# Board.net
KiCad netlist of a schematic drawn in EAGLE
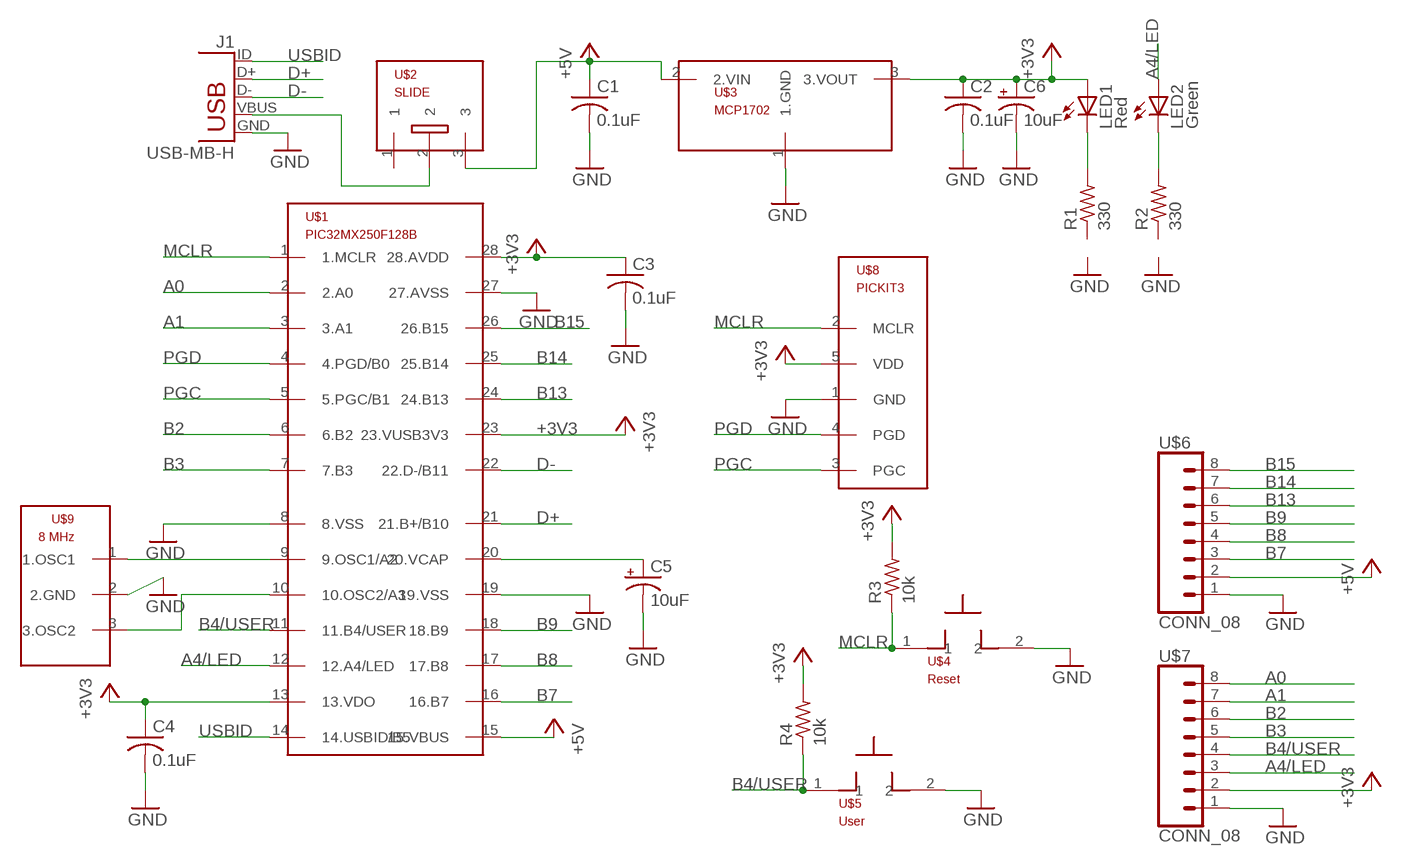
[diagram p0: schematic, sheet 1]

(export (version "E")
  (design (tool "Eeschema 10.0.6"))
  (components
    (comp (ref "C1")
      (value "0.1uF")
      (footprint "eagle-import:C025-025X050")
      (libsource (lib "eagle-import") (part "C-US025-025X050"))
    )
    (comp (ref "C2")
      (value "0.1uF")
      (footprint "eagle-import:C025-025X050")
      (libsource (lib "eagle-import") (part "C-US025-025X050"))
    )
    (comp (ref "C3")
      (value "0.1uF")
      (footprint "eagle-import:C025-025X050")
      (libsource (lib "eagle-import") (part "C-US025-025X050"))
    )
    (comp (ref "C4")
      (value "0.1uF")
      (footprint "eagle-import:C025-025X050")
      (libsource (lib "eagle-import") (part "C-US025-025X050"))
    )
    (comp (ref "C5")
      (value "10uF")
      (footprint "eagle-import:B45181B")
      (libsource (lib "eagle-import") (part "CPOL-USB45181B"))
    )
    (comp (ref "C6")
      (value "10uF")
      (footprint "eagle-import:B45181B")
      (libsource (lib "eagle-import") (part "CPOL-USB45181B"))
    )
    (comp (ref "J1")
      (value "USB-MB-H")
      (footprint "eagle-import:USB-MB-H")
      (libsource (lib "eagle-import") (part "USB-MB-H"))
    )
    (comp (ref "LED1")
      (value "Red")
      (footprint "eagle-import:LED3MM")
      (libsource (lib "eagle-import") (part "LED3MM"))
    )
    (comp (ref "LED2")
      (value "Green")
      (footprint "eagle-import:LED3MM")
      (libsource (lib "eagle-import") (part "LED3MM"))
    )
    (comp (ref "R1")
      (value "330")
      (footprint "eagle-import:0207_10")
      (libsource (lib "eagle-import") (part "R-US_0207/10"))
    )
    (comp (ref "R2")
      (value "330")
      (footprint "eagle-import:0207_10")
      (libsource (lib "eagle-import") (part "R-US_0207/10"))
    )
    (comp (ref "R3")
      (value "10k")
      (footprint "eagle-import:0207_10")
      (libsource (lib "eagle-import") (part "R-US_0207/10"))
    )
    (comp (ref "R4")
      (value "10k")
      (footprint "eagle-import:0207_10")
      (libsource (lib "eagle-import") (part "R-US_0207/10"))
    )
    (comp (ref "U$1")
      (value "PIC32MX250F128B")
      (footprint "eagle-import:DIL28-3")
      (libsource (lib "eagle-import") (part "PIC32MX250F128B"))
    )
    (comp (ref "U$2")
      (value "SLIDE")
      (footprint "eagle-import:SLIDE")
      (libsource (lib "eagle-import") (part "SLIDE"))
    )
    (comp (ref "U$3")
      (value "MCP1702")
      (footprint "eagle-import:TO92")
      (libsource (lib "eagle-import") (part "MCP1702"))
    )
    (comp (ref "U$4")
      (value "Reset")
      (footprint "eagle-import:PB")
      (libsource (lib "eagle-import") (part "PB"))
    )
    (comp (ref "U$5")
      (value "User")
      (footprint "eagle-import:PB")
      (libsource (lib "eagle-import") (part "PB"))
    )
    (comp (ref "U$6")
      (value "CONN_08")
      (footprint "eagle-import:1X08")
      (libsource (lib "eagle-import") (part "CONN_08"))
    )
    (comp (ref "U$7")
      (value "CONN_08")
      (footprint "eagle-import:1X08")
      (libsource (lib "eagle-import") (part "CONN_08"))
    )
    (comp (ref "U$8")
      (value "PICKIT3")
      (footprint "eagle-import:1X05")
      (libsource (lib "eagle-import") (part "PICKIT3"))
    )
    (comp (ref "U$9")
      (value "8 MHz")
      (footprint "eagle-import:OSC")
      (libsource (lib "eagle-import") (part "OSC"))
    )
  )
  (nets
    (net (code "1") (name "+3V3") (class "Default")
      (node (ref "C2") (pin "1") (pinfunction "1_1") (pintype "passive"))
      (node (ref "C3") (pin "1") (pinfunction "1_1") (pintype "passive"))
      (node (ref "C4") (pin "1") (pinfunction "1_1") (pintype "passive"))
      (node (ref "C6") (pin "+") (pinfunction "+_+") (pintype "passive"))
      (node (ref "LED1") (pin "A") (pinfunction "A_A") (pintype "passive"))
      (node (ref "R3") (pin "2") (pinfunction "2_2") (pintype "passive"))
      (node (ref "R4") (pin "2") (pinfunction "2_2") (pintype "passive"))
      (node (ref "U$1") (pin "13") (pinfunction "13.VDO_13") (pintype "bidirectional"))
      (node (ref "U$1") (pin "23") (pinfunction "23.VUSB3V3_23") (pintype "bidirectional"))
      (node (ref "U$1") (pin "28") (pinfunction "28.AVDD_28") (pintype "bidirectional"))
      (node (ref "U$3") (pin "3") (pinfunction "3.VOUT_3") (pintype "bidirectional"))
      (node (ref "U$7") (pin "2") (pinfunction "2_2") (pintype "passive"))
      (node (ref "U$8") (pin "5") (pinfunction "VDD_5") (pintype "bidirectional"))
    )
    (net (code "2") (name "+5V") (class "Default")
      (node (ref "C1") (pin "1") (pinfunction "1_1") (pintype "passive"))
      (node (ref "U$1") (pin "15") (pinfunction "15.VBUS_15") (pintype "bidirectional"))
      (node (ref "U$2") (pin "3") (pinfunction "3_3") (pintype "bidirectional"))
      (node (ref "U$3") (pin "2") (pinfunction "2.VIN_2") (pintype "bidirectional"))
      (node (ref "U$6") (pin "2") (pinfunction "2_2") (pintype "passive"))
    )
    (net (code "3") (name "/A0") (class "Default")
      (node (ref "U$1") (pin "2") (pinfunction "2.A0_2") (pintype "bidirectional"))
      (node (ref "U$7") (pin "8") (pinfunction "8_8") (pintype "passive"))
    )
    (net (code "4") (name "/A1") (class "Default")
      (node (ref "U$1") (pin "3") (pinfunction "3.A1_3") (pintype "bidirectional"))
      (node (ref "U$7") (pin "7") (pinfunction "7_7") (pintype "passive"))
    )
    (net (code "5") (name "/A4{slash}LED") (class "Default")
      (node (ref "LED2") (pin "A") (pinfunction "A_A") (pintype "passive"))
      (node (ref "U$1") (pin "12") (pinfunction "12.A4/LED_12") (pintype "bidirectional"))
      (node (ref "U$7") (pin "3") (pinfunction "3_3") (pintype "passive"))
    )
    (net (code "6") (name "/B2") (class "Default")
      (node (ref "U$1") (pin "6") (pinfunction "6.B2_6") (pintype "bidirectional"))
      (node (ref "U$7") (pin "6") (pinfunction "6_6") (pintype "passive"))
    )
    (net (code "7") (name "/B3") (class "Default")
      (node (ref "U$1") (pin "7") (pinfunction "7.B3_7") (pintype "bidirectional"))
      (node (ref "U$7") (pin "5") (pinfunction "5_5") (pintype "passive"))
    )
    (net (code "8") (name "/B4{slash}USER") (class "Default")
      (node (ref "R4") (pin "1") (pinfunction "1_1") (pintype "passive"))
      (node (ref "U$1") (pin "11") (pinfunction "11.B4/USER_11") (pintype "bidirectional"))
      (node (ref "U$5") (pin "1") (pinfunction "1_1") (pintype "bidirectional"))
      (node (ref "U$7") (pin "4") (pinfunction "4_4") (pintype "passive"))
    )
    (net (code "9") (name "/B7") (class "Default")
      (node (ref "U$1") (pin "16") (pinfunction "16.B7_16") (pintype "bidirectional"))
      (node (ref "U$6") (pin "3") (pinfunction "3_3") (pintype "passive"))
    )
    (net (code "10") (name "/B8") (class "Default")
      (node (ref "U$1") (pin "17") (pinfunction "17.B8_17") (pintype "bidirectional"))
      (node (ref "U$6") (pin "4") (pinfunction "4_4") (pintype "passive"))
    )
    (net (code "11") (name "/B9") (class "Default")
      (node (ref "U$1") (pin "18") (pinfunction "18.B9_18") (pintype "bidirectional"))
      (node (ref "U$6") (pin "5") (pinfunction "5_5") (pintype "passive"))
    )
    (net (code "12") (name "/B13") (class "Default")
      (node (ref "U$1") (pin "24") (pinfunction "24.B13_24") (pintype "bidirectional"))
      (node (ref "U$6") (pin "6") (pinfunction "6_6") (pintype "passive"))
    )
    (net (code "13") (name "/B14") (class "Default")
      (node (ref "U$1") (pin "25") (pinfunction "25.B14_25") (pintype "bidirectional"))
      (node (ref "U$6") (pin "7") (pinfunction "7_7") (pintype "passive"))
    )
    (net (code "14") (name "/B15") (class "Default")
      (node (ref "U$1") (pin "26") (pinfunction "26.B15_26") (pintype "bidirectional"))
      (node (ref "U$6") (pin "8") (pinfunction "8_8") (pintype "passive"))
    )
    (net (code "15") (name "/D+") (class "Default")
      (node (ref "J1") (pin "D+") (pinfunction "D+_D+") (pintype "bidirectional"))
      (node (ref "U$1") (pin "21") (pinfunction "21.B+/B10_21") (pintype "bidirectional"))
    )
    (net (code "16") (name "/D-") (class "Default")
      (node (ref "J1") (pin "D-") (pinfunction "D-_D-") (pintype "bidirectional"))
      (node (ref "U$1") (pin "22") (pinfunction "22.D-/B11_22") (pintype "bidirectional"))
    )
    (net (code "17") (name "/MCLR") (class "Default")
      (node (ref "R3") (pin "1") (pinfunction "1_1") (pintype "passive"))
      (node (ref "U$1") (pin "1") (pinfunction "1.MCLR_1") (pintype "bidirectional"))
      (node (ref "U$4") (pin "1") (pinfunction "1_1") (pintype "bidirectional"))
      (node (ref "U$8") (pin "2") (pinfunction "MCLR_2") (pintype "bidirectional"))
    )
    (net (code "18") (name "/PGC") (class "Default")
      (node (ref "U$1") (pin "5") (pinfunction "5.PGC/B1_5") (pintype "bidirectional"))
      (node (ref "U$8") (pin "3") (pinfunction "PGC_3") (pintype "bidirectional"))
    )
    (net (code "19") (name "/PGD") (class "Default")
      (node (ref "U$1") (pin "4") (pinfunction "4.PGD/B0_4") (pintype "bidirectional"))
      (node (ref "U$8") (pin "4") (pinfunction "PGD_4") (pintype "bidirectional"))
    )
    (net (code "20") (name "/USBID") (class "Default")
      (node (ref "J1") (pin "ID") (pinfunction "ID_ID") (pintype "bidirectional"))
      (node (ref "U$1") (pin "14") (pinfunction "14.USBID/B5_14") (pintype "bidirectional"))
    )
    (net (code "21") (name "GND") (class "Default")
      (node (ref "C1") (pin "2") (pinfunction "2_2") (pintype "passive"))
      (node (ref "C2") (pin "2") (pinfunction "2_2") (pintype "passive"))
      (node (ref "C3") (pin "2") (pinfunction "2_2") (pintype "passive"))
      (node (ref "C4") (pin "2") (pinfunction "2_2") (pintype "passive"))
      (node (ref "C5") (pin "-") (pinfunction "-_-") (pintype "passive"))
      (node (ref "C6") (pin "-") (pinfunction "-_-") (pintype "passive"))
      (node (ref "J1") (pin "GND") (pinfunction "GND_GND") (pintype "bidirectional"))
      (node (ref "U$1") (pin "19") (pinfunction "19.VSS_19") (pintype "bidirectional"))
      (node (ref "U$1") (pin "27") (pinfunction "27.AVSS_27") (pintype "bidirectional"))
      (node (ref "U$1") (pin "8") (pinfunction "8.VSS_8") (pintype "bidirectional"))
      (node (ref "U$3") (pin "1") (pinfunction "1.GND_1") (pintype "bidirectional"))
      (node (ref "U$4") (pin "2") (pinfunction "2_2") (pintype "bidirectional"))
      (node (ref "U$5") (pin "2") (pinfunction "2_2") (pintype "bidirectional"))
      (node (ref "U$6") (pin "1") (pinfunction "1_1") (pintype "passive"))
      (node (ref "U$7") (pin "1") (pinfunction "1_1") (pintype "passive"))
      (node (ref "U$8") (pin "1") (pinfunction "GND_1") (pintype "bidirectional"))
      (node (ref "U$9") (pin "2") (pinfunction "2.GND_2") (pintype "bidirectional"))
    )
    (net (code "22") (name "Net-(J1-PadVBUS)") (class "Default")
      (node (ref "J1") (pin "VBUS") (pinfunction "VBUS_VBUS") (pintype "bidirectional"))
      (node (ref "U$2") (pin "2") (pinfunction "2_2") (pintype "bidirectional"))
    )
    (net (code "23") (name "Net-(LED1-C)") (class "Default")
      (node (ref "LED1") (pin "K") (pinfunction "C_K") (pintype "passive"))
      (node (ref "R1") (pin "2") (pinfunction "2_2") (pintype "passive"))
    )
    (net (code "24") (name "Net-(LED2-C)") (class "Default")
      (node (ref "LED2") (pin "K") (pinfunction "C_K") (pintype "passive"))
      (node (ref "R2") (pin "2") (pinfunction "2_2") (pintype "passive"))
    )
    (net (code "25") (name "Net-(U$1-9.OSC1{slash}A2)") (class "Default")
      (node (ref "U$1") (pin "9") (pinfunction "9.OSC1/A2_9") (pintype "bidirectional"))
      (node (ref "U$9") (pin "1") (pinfunction "1.OSC1_1") (pintype "bidirectional"))
    )
    (net (code "26") (name "Net-(U$1-10.OSC2{slash}A3)") (class "Default")
      (node (ref "U$1") (pin "10") (pinfunction "10.OSC2/A3_10") (pintype "bidirectional"))
      (node (ref "U$9") (pin "3") (pinfunction "3.OSC2_3") (pintype "bidirectional"))
    )
    (net (code "27") (name "Net-(U$1-20.VCAP)") (class "Default")
      (node (ref "C5") (pin "+") (pinfunction "+_+") (pintype "passive"))
      (node (ref "U$1") (pin "20") (pinfunction "20.VCAP_20") (pintype "bidirectional"))
    )
    (net (code "28") (name "unconnected-(R1-Pad1)") (class "Default")
      (node (ref "R1") (pin "1") (pinfunction "1_1") (pintype "passive"))
    )
    (net (code "29") (name "unconnected-(R2-Pad1)") (class "Default")
      (node (ref "R2") (pin "1") (pinfunction "1_1") (pintype "passive"))
    )
    (net (code "30") (name "unconnected-(U$2-Pad1)") (class "Default")
      (node (ref "U$2") (pin "1") (pinfunction "1_1") (pintype "bidirectional"))
    )
  )
)
